# BSE_SCH.net
KiCad netlist of a schematic drawn in Altium Designer
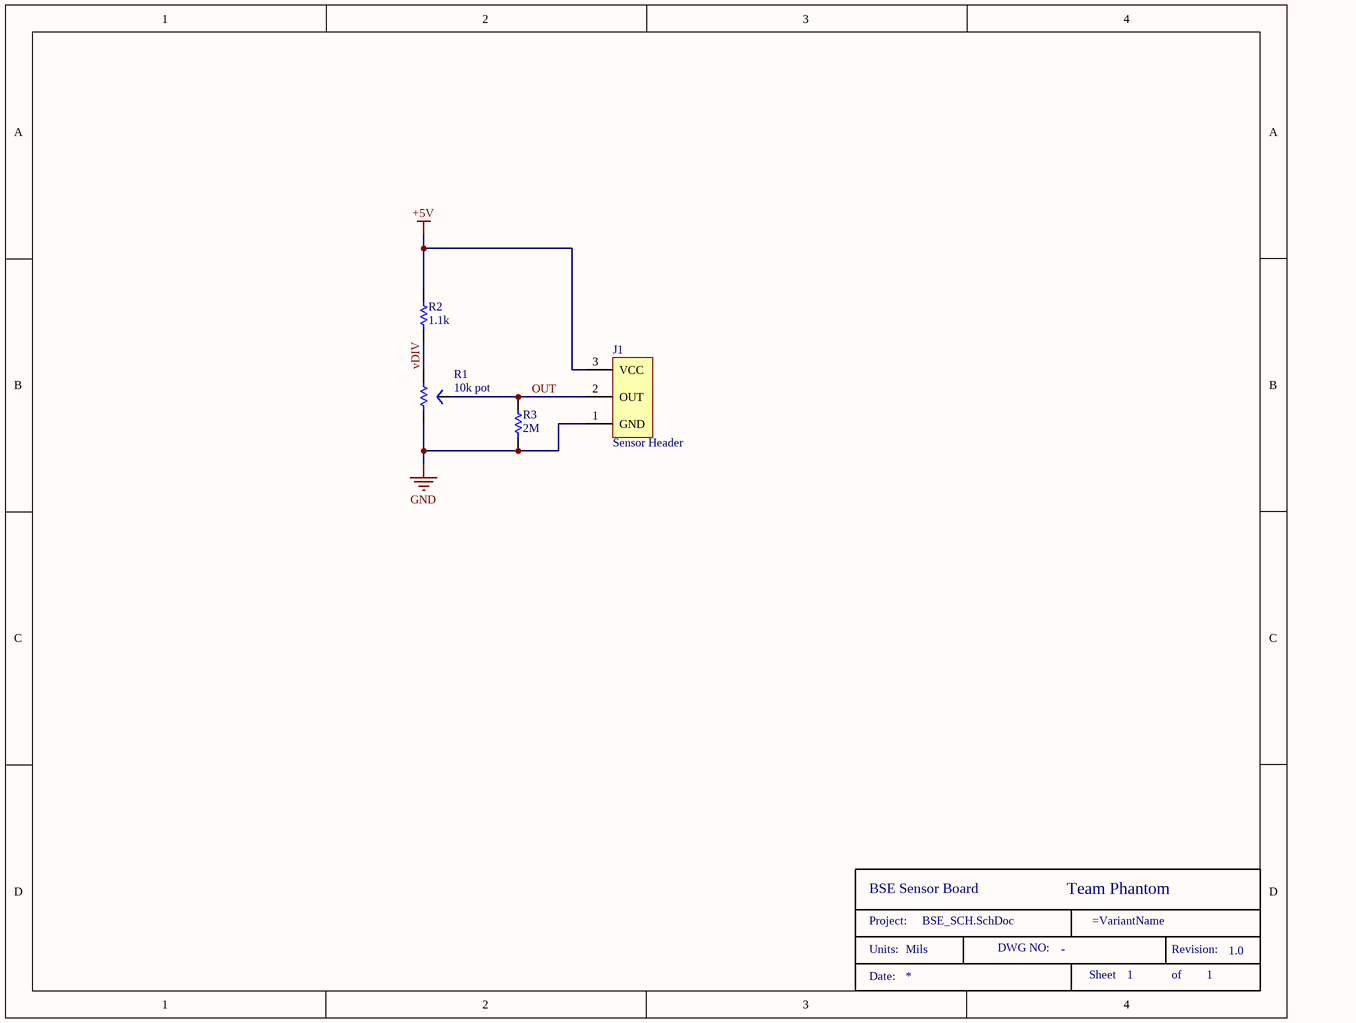
[diagram p0: BSE_SCH.SchDoc]

(export (version "E")
  (design (tool "Eeschema 10.0.6"))
  (components
    (comp (ref "*")
      (value "TitleBlock")
      (description "TItle Block")
      (libsource (lib "BSE_SCH_lib") (part "TitleBlock"))
    )
    (comp (ref "J1")
      (value "Sensor Header")
      (footprint "3PIN")
      (description "CONN HEADER R/A 3POS 2.54MM")
      (fields (field (name "MANUFACTURER") "Molex") (field (name "MANUFACTURER PART NUMBER") "70553-0002"))
      (libsource (lib "BSE_SCH_lib") (part "3PIN"))
    )
    (comp (ref "R1")
      (value "10k pot")
      (footprint "10k Rotary Encoder")
      (description "Res Cermet Trimmer 10K Ohm 30% 1(Elec)/1(Mech)Turn 4mm (11 X 14.9 X 3.1mm) Gull Wing SMD T/R")
      (fields
        (field (name "MANUFACTURER") "Murata")
        (field (name "MANUFACTURER PART NUMBER") "SV01A103AEA01R00")
      )
      (libsource (lib "BSE_SCH_lib") (part "10k rotary encoder"))
    )
    (comp (ref "R2")
      (value "1.1k")
      (footprint "RES 0603")
      (description "ERJPA3 Resistors 0.25W 0603 1K1 1%")
      (fields
        (field (name "MANUFACTURER") "Panasonic")
        (field (name "MANUFACTURER PART NUMBER") "ERJ-PA3F1101V")
      )
      (libsource (lib "BSE_SCH_lib") (part "RES 1.1k"))
    )
    (comp (ref "R3")
      (value "2M")
      (footprint "RES 0603")
      (description "Res Thick Film 0603 2MegaOhm 1% 1/4W ±100ppm/K Molded Paper T/R")
      (fields
        (field (name "MANUFACTURER") "Vishay")
        (field (name "MANUFACTURER PART NUMBER") "RCS06032M00FKEA")
      )
      (libsource (lib "BSE_SCH_lib") (part "RES 2M"))
    )
  )
  (nets
    (net (code "1") (name "+5V") (class "Default")
      (node (ref "J1") (pin "3") (pinfunction "VCC_3") (pintype "passive"))
      (node (ref "R2") (pin "2") (pinfunction "2_2") (pintype "passive"))
    )
    (net (code "2") (name "/OUT") (class "Default")
      (node (ref "J1") (pin "2") (pinfunction "OUT_2") (pintype "passive"))
      (node (ref "R1") (pin "2") (pinfunction "2_2") (pintype "passive"))
      (node (ref "R3") (pin "2") (pinfunction "2_2") (pintype "passive"))
    )
    (net (code "3") (name "/vDIV") (class "Default")
      (node (ref "R1") (pin "3") (pinfunction "3_3") (pintype "passive"))
      (node (ref "R2") (pin "1") (pinfunction "1_1") (pintype "passive"))
    )
    (net (code "4") (name "GND") (class "Default")
      (node (ref "J1") (pin "1") (pinfunction "GND_1") (pintype "passive"))
      (node (ref "R1") (pin "1") (pinfunction "1_1") (pintype "passive"))
      (node (ref "R3") (pin "1") (pinfunction "1_1") (pintype "passive"))
    )
  )
)
